# PCB-REMCON-E.net
KiCad netlist of a schematic drawn in EAGLE
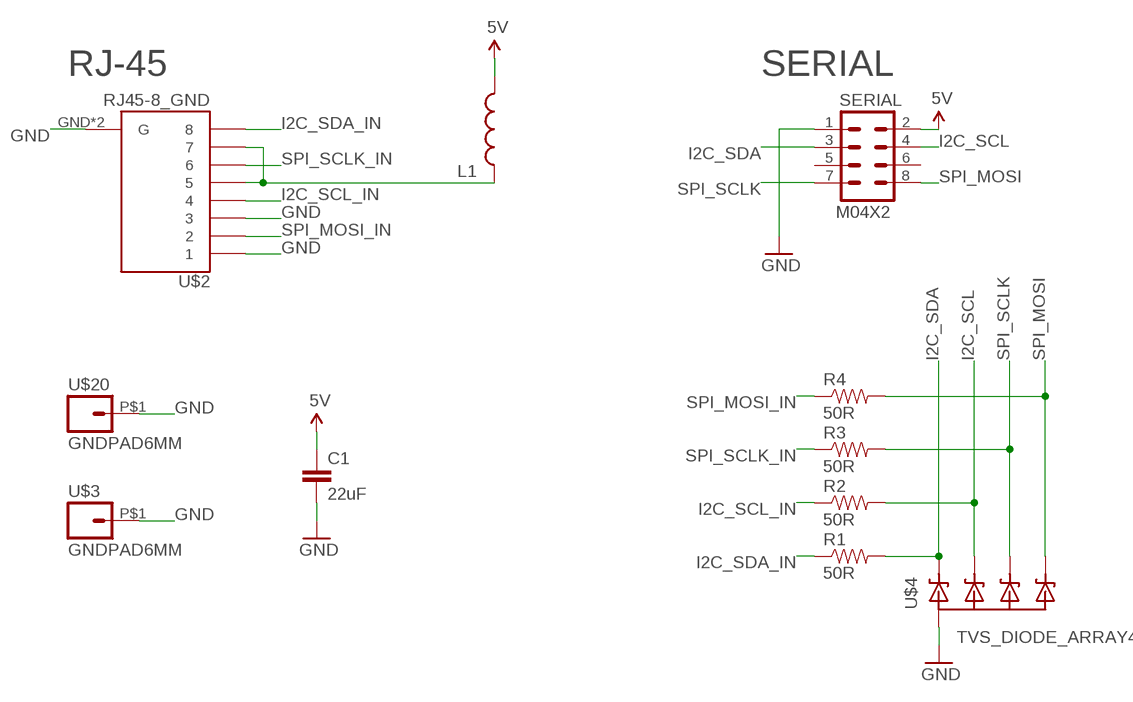
[diagram p0: schematic, sheet 1]

(export (version "E")
  (design (tool "Eeschema 10.0.6"))
  (components
    (comp (ref "C1")
      (value "22uF")
      (footprint "eagle-import:0805")
      (libsource (lib "eagle-import") (part "CAP0805"))
    )
    (comp (ref "L1")
      (value "INDUCTOR0805")
      (footprint "eagle-import:0805")
      (libsource (lib "eagle-import") (part "INDUCTOR0805"))
    )
    (comp (ref "R1")
      (value "50R")
      (footprint "eagle-import:0603-RES")
      (libsource (lib "eagle-import") (part "RESISTOR0603-RES"))
    )
    (comp (ref "R2")
      (value "50R")
      (footprint "eagle-import:0603-RES")
      (libsource (lib "eagle-import") (part "RESISTOR0603-RES"))
    )
    (comp (ref "R3")
      (value "50R")
      (footprint "eagle-import:0603-RES")
      (libsource (lib "eagle-import") (part "RESISTOR0603-RES"))
    )
    (comp (ref "R4")
      (value "50R")
      (footprint "eagle-import:0603-RES")
      (libsource (lib "eagle-import") (part "RESISTOR0603-RES"))
    )
    (comp (ref "SERIAL")
      (value "M04X2")
      (footprint "eagle-import:2X4")
      (libsource (lib "eagle-import") (part "M04X2"))
    )
    (comp (ref "U$2")
      (value "RJ45-8_GND")
      (footprint "eagle-import:RJ45-8_GND")
      (libsource (lib "eagle-import") (part "RJ45-8_GND"))
    )
    (comp (ref "U$3")
      (value "GNDPAD6MM")
      (footprint "eagle-import:3.2MMPAD6MM")
      (libsource (lib "eagle-import") (part "GNDPAD6MM"))
    )
    (comp (ref "U$4")
      (value "TVS_DIODE_ARRAY4")
      (footprint "eagle-import:SOT23-6L")
      (libsource (lib "eagle-import") (part "TVS_DIODE_ARRAY4"))
    )
    (comp (ref "U$20")
      (value "GNDPAD6MM")
      (footprint "eagle-import:3.2MMPAD6MM")
      (libsource (lib "eagle-import") (part "GNDPAD6MM"))
    )
  )
  (nets
    (net (code "1") (name "/I2C_SCL") (class "Default")
      (node (ref "R2") (pin "2") (pinfunction "2_2") (pintype "passive"))
      (node (ref "SERIAL") (pin "4") (pinfunction "4_4") (pintype "passive"))
      (node (ref "U$4") (pin "3") (pinfunction "B_3") (pintype "passive"))
    )
    (net (code "2") (name "/I2C_SCL_IN") (class "Default")
      (node (ref "R2") (pin "1") (pinfunction "1_1") (pintype "passive"))
      (node (ref "U$2") (pin "4") (pinfunction "4_4") (pintype "bidirectional"))
    )
    (net (code "3") (name "/I2C_SDA") (class "Default")
      (node (ref "R1") (pin "2") (pinfunction "2_2") (pintype "passive"))
      (node (ref "SERIAL") (pin "3") (pinfunction "3_3") (pintype "passive"))
      (node (ref "U$4") (pin "1") (pinfunction "A_1") (pintype "passive"))
    )
    (net (code "4") (name "/I2C_SDA_IN") (class "Default")
      (node (ref "R1") (pin "1") (pinfunction "1_1") (pintype "passive"))
      (node (ref "U$2") (pin "8") (pinfunction "8_8") (pintype "bidirectional"))
    )
    (net (code "5") (name "/SPI_MOSI") (class "Default")
      (node (ref "R4") (pin "2") (pinfunction "2_2") (pintype "passive"))
      (node (ref "SERIAL") (pin "8") (pinfunction "8_8") (pintype "passive"))
      (node (ref "U$4") (pin "6") (pinfunction "D_6") (pintype "passive"))
    )
    (net (code "6") (name "/SPI_MOSI_IN") (class "Default")
      (node (ref "R4") (pin "1") (pinfunction "1_1") (pintype "passive"))
      (node (ref "U$2") (pin "2") (pinfunction "2_2") (pintype "bidirectional"))
    )
    (net (code "7") (name "/SPI_SCLK") (class "Default")
      (node (ref "R3") (pin "2") (pinfunction "2_2") (pintype "passive"))
      (node (ref "SERIAL") (pin "7") (pinfunction "7_7") (pintype "passive"))
      (node (ref "U$4") (pin "4") (pinfunction "C_4") (pintype "passive"))
    )
    (net (code "8") (name "/SPI_SCLK_IN") (class "Default")
      (node (ref "R3") (pin "1") (pinfunction "1_1") (pintype "passive"))
      (node (ref "U$2") (pin "6") (pinfunction "6_6") (pintype "bidirectional"))
    )
    (net (code "9") (name "5V") (class "Default")
      (node (ref "C1") (pin "1") (pinfunction "1_1") (pintype "passive"))
      (node (ref "L1") (pin "2") (pinfunction "2_2") (pintype "passive"))
      (node (ref "SERIAL") (pin "2") (pinfunction "2_2") (pintype "passive"))
    )
    (net (code "10") (name "GND") (class "Default")
      (node (ref "C1") (pin "2") (pinfunction "2_2") (pintype "passive"))
      (node (ref "SERIAL") (pin "1") (pinfunction "1_1") (pintype "passive"))
      (node (ref "U$2") (pin "1") (pinfunction "1_1") (pintype "bidirectional"))
      (node (ref "U$2") (pin "3") (pinfunction "3_3") (pintype "bidirectional"))
      (node (ref "U$2") (pin "GND") (pinfunction "G_GND") (pintype "power_in"))
      (node (ref "U$2") (pin "GND1") (pinfunction "G_GND1") (pintype "power_in"))
      (node (ref "U$20") (pin "P$1") (pinfunction "1_P$1") (pintype "passive"))
      (node (ref "U$3") (pin "P$1") (pinfunction "1_P$1") (pintype "passive"))
      (node (ref "U$4") (pin "2") (pinfunction "GND_2") (pintype "passive"))
      (node (ref "U$4") (pin "5") (pinfunction "GND_5") (pintype "passive"))
    )
    (net (code "11") (name "Net-(L1-Pad1)") (class "Default")
      (node (ref "L1") (pin "1") (pinfunction "1_1") (pintype "passive"))
      (node (ref "U$2") (pin "5") (pinfunction "5_5") (pintype "bidirectional"))
      (node (ref "U$2") (pin "7") (pinfunction "7_7") (pintype "bidirectional"))
    )
    (net (code "12") (name "unconnected-(SERIAL-Pad5)") (class "Default")
      (node (ref "SERIAL") (pin "5") (pinfunction "5_5") (pintype "passive"))
    )
    (net (code "13") (name "unconnected-(SERIAL-Pad6)") (class "Default")
      (node (ref "SERIAL") (pin "6") (pinfunction "6_6") (pintype "passive"))
    )
  )
)
